# v0_2.net
KiCad netlist of a schematic drawn in EAGLE
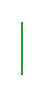
[diagram p0: schematic, sheet 1, part 1 of 2]
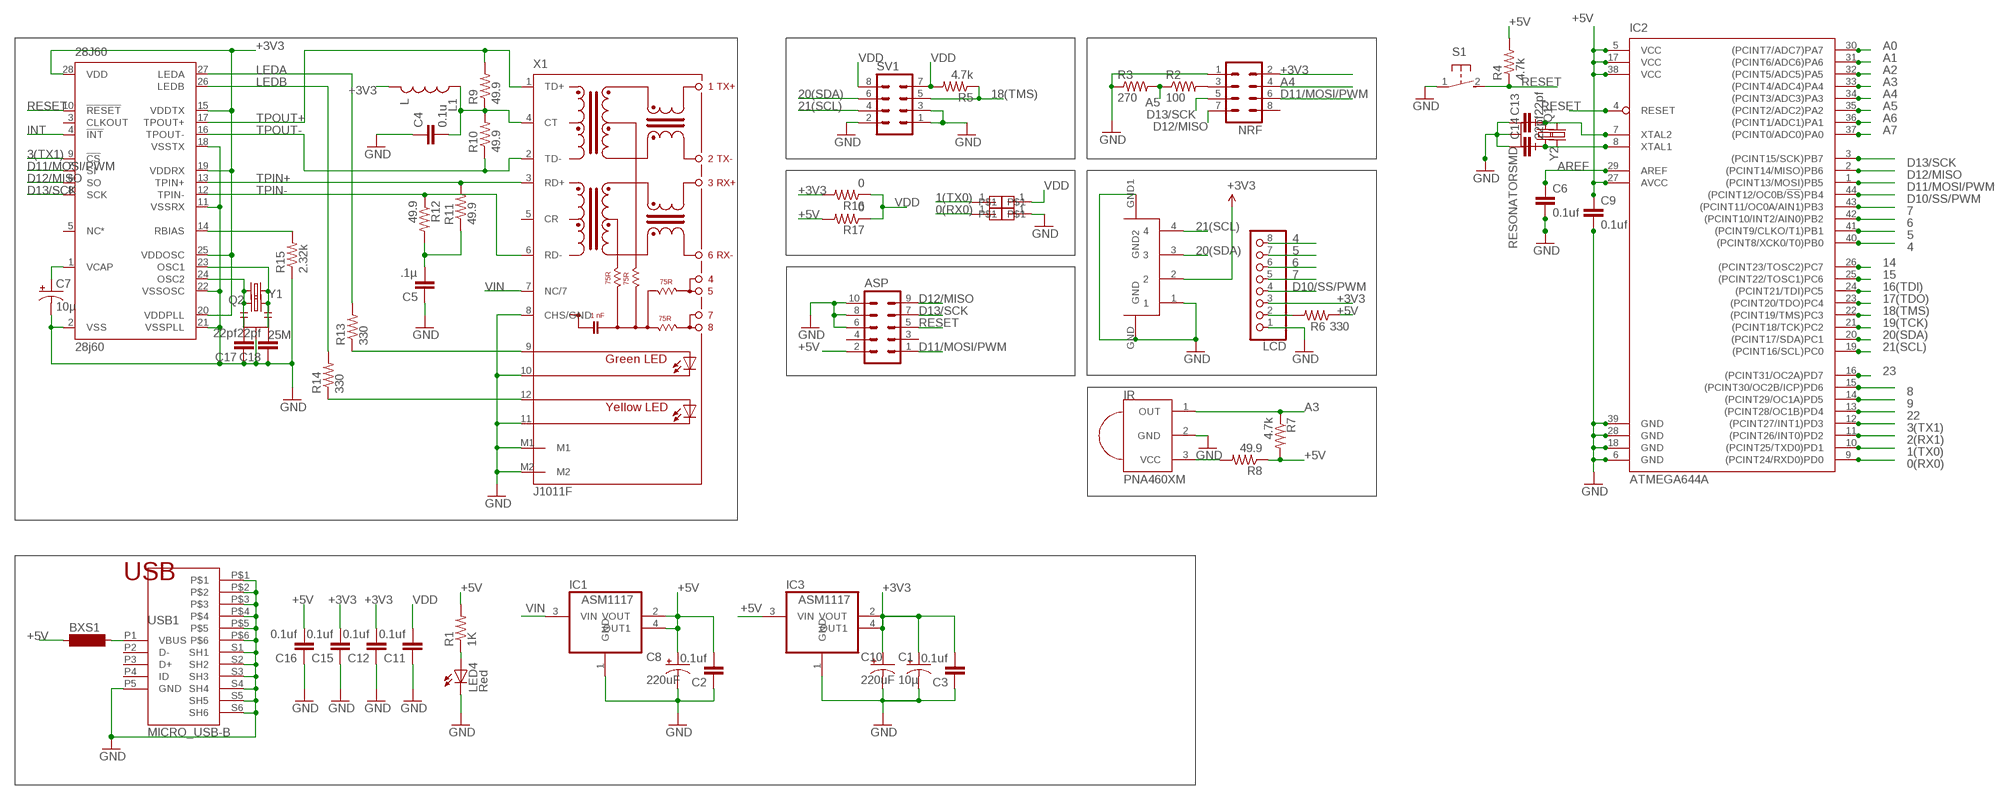
[diagram p1: schematic, sheet 1, part 2 of 2]

(export (version "E")
  (design (tool "Eeschema 10.0.6"))
  (components
    (comp (ref "28J60")
      (value "28j60")
      (footprint "eagle-import:SSOP28DB")
      (libsource (lib "eagle-import") (part "ENC28J60/SS"))
    )
    (comp (ref "ASP")
      (value "MA05-2")
      (footprint "eagle-import:MA05-2")
      (libsource (lib "eagle-import") (part "MA05-2"))
    )
    (comp (ref "BXS1")
      (value "SM-1206")
      (footprint "eagle-import:SM-1206")
      (fields (field (name "OC_FARNELL") "unknown") (field (name "OC_NEWARK") "unknown"))
      (libsource (lib "eagle-import") (part "SM-1206"))
    )
    (comp (ref "C1")
      (value "10µ")
      (footprint "eagle-import:EIA3528")
      (libsource (lib "eagle-import") (part "CAP_POL3528"))
    )
    (comp (ref "C2")
      (value "0.1uf")
      (footprint "eagle-import:0603-CAP")
      (libsource (lib "eagle-import") (part "MY_CAP0603-CAP"))
    )
    (comp (ref "C3")
      (value "0.1uf")
      (footprint "eagle-import:0603-CAP")
      (libsource (lib "eagle-import") (part "MY_CAP0603-CAP"))
    )
    (comp (ref "C4")
      (value "0.1u")
      (footprint "eagle-import:0603-CAP")
      (libsource (lib "eagle-import") (part "CAP0603-CAP"))
    )
    (comp (ref "C5")
      (value ".1µ")
      (footprint "eagle-import:0603-CAP")
      (libsource (lib "eagle-import") (part "CAP0603-CAP"))
    )
    (comp (ref "C6")
      (value "0.1uf")
      (footprint "eagle-import:0603-CAP")
      (libsource (lib "eagle-import") (part "CAP0603-CAP"))
    )
    (comp (ref "C7")
      (value "10µ")
      (footprint "eagle-import:EIA3528")
      (libsource (lib "eagle-import") (part "CAP_POL3528"))
    )
    (comp (ref "C8")
      (value "220uF")
      (footprint "eagle-import:153CLV-0605")
      (libsource (lib "eagle-import") (part "CPOL-US153CLV-0605"))
    )
    (comp (ref "C9")
      (value "0.1uf")
      (footprint "eagle-import:0603-CAP")
      (libsource (lib "eagle-import") (part "CAP0603-CAP"))
    )
    (comp (ref "C10")
      (value "220uF")
      (footprint "eagle-import:153CLV-0605")
      (libsource (lib "eagle-import") (part "CPOL-US153CLV-0605"))
    )
    (comp (ref "C11")
      (value "0.1uf")
      (footprint "eagle-import:0603-CAP")
      (libsource (lib "eagle-import") (part "MY_CAP0603-CAP"))
    )
    (comp (ref "C12")
      (value "0.1uf")
      (footprint "eagle-import:0603-CAP")
      (libsource (lib "eagle-import") (part "MY_CAP0603-CAP"))
    )
    (comp (ref "C13")
      (value "22pf")
      (footprint "eagle-import:0603-CAP")
      (libsource (lib "eagle-import") (part "CAP0603-CAP"))
    )
    (comp (ref "C14")
      (value "22pf")
      (footprint "eagle-import:0603-CAP")
      (libsource (lib "eagle-import") (part "CAP0603-CAP"))
    )
    (comp (ref "C15")
      (value "0.1uf")
      (footprint "eagle-import:0603-CAP")
      (libsource (lib "eagle-import") (part "MY_CAP0603-CAP"))
    )
    (comp (ref "C16")
      (value "0.1uf")
      (footprint "eagle-import:0603-CAP")
      (libsource (lib "eagle-import") (part "MY_CAP0603-CAP"))
    )
    (comp (ref "C17")
      (value "22pf")
      (footprint "eagle-import:0603-CAP")
      (libsource (lib "eagle-import") (part "CAP0603-CAP"))
    )
    (comp (ref "C18")
      (value "22pf")
      (footprint "eagle-import:0603-CAP")
      (libsource (lib "eagle-import") (part "CAP0603-CAP"))
    )
    (comp (ref "IC1")
      (value "ASM1117")
      (footprint "eagle-import:SOT223")
      (fields (field (name "MPN") "REG1117"))
      (libsource (lib "eagle-import") (part "ASM1117"))
    )
    (comp (ref "IC2")
      (value "ATMEGA644A")
      (footprint "eagle-import:TQFP44")
      (fields (field (name "MPN") "ATMEGA644PV-10AU"))
      (libsource (lib "eagle-import") (part "ATMEGA644A"))
    )
    (comp (ref "IC3")
      (value "ASM1117")
      (footprint "eagle-import:SOT223")
      (fields
        (field (name "MPN") "REG1117")
        (field (name "MPN_1") "REG1117")
        (field (name "OC_FARNELL") "1097566")
        (field (name "OC_NEWARK") "14P6981")
      )
      (libsource (lib "eagle-import") (part "ASM1117"))
    )
    (comp (ref "IR")
      (value "PNA460XM")
      (footprint "eagle-import:PNA460XM")
      (libsource (lib "eagle-import") (part "PNA460XM"))
    )
    (comp (ref "L1")
      (value "L")
      (footprint "eagle-import:0603")
      (libsource (lib "eagle-import") (part "INDUCTOR0603"))
    )
    (comp (ref "LCD")
      (value "PINHD-1X8")
      (footprint "eagle-import:1X08")
      (libsource (lib "eagle-import") (part "PINHD-1X8"))
    )
    (comp (ref "LED4")
      (value "Red")
      (footprint "eagle-import:0805-LED")
      (libsource (lib "eagle-import") (part "LED0805"))
    )
    (comp (ref "NRF")
      (value "MA04-2")
      (footprint "eagle-import:MA04-2")
      (libsource (lib "eagle-import") (part "MA04-2"))
    )
    (comp (ref "Q1")
      (value "CRYSTALHC49S")
      (footprint "eagle-import:HC49_S")
      (libsource (lib "eagle-import") (part "CRYSTALHC49S"))
    )
    (comp (ref "Q2")
      (value "CRYSTALHC49S")
      (footprint "eagle-import:HC49_S")
      (fields (field (name "OC_FARNELL") "1667008") (field (name "OC_NEWARK") "unknown"))
      (libsource (lib "eagle-import") (part "CRYSTALHC49S"))
    )
    (comp (ref "R1")
      (value "1K")
      (footprint "eagle-import:0603-RES")
      (libsource (lib "eagle-import") (part "MY_RESISTOR0603-RES"))
    )
    (comp (ref "R2")
      (value "100")
      (footprint "eagle-import:0603-RES")
      (libsource (lib "eagle-import") (part "MY_RESISTOR0603-RES"))
    )
    (comp (ref "R3")
      (value "270")
      (footprint "eagle-import:0603-RES")
      (libsource (lib "eagle-import") (part "MY_RESISTOR0603-RES"))
    )
    (comp (ref "R4")
      (value "4.7k")
      (footprint "eagle-import:0603-RES")
      (libsource (lib "eagle-import") (part "RESISTOR0603-RES"))
    )
    (comp (ref "R5")
      (value "4.7k")
      (footprint "eagle-import:0603-RES")
      (libsource (lib "eagle-import") (part "MY_RESISTOR0603-RES"))
    )
    (comp (ref "R6")
      (value "330")
      (footprint "eagle-import:0603-RES")
      (libsource (lib "eagle-import") (part "MY_RESISTOR0603-RES"))
    )
    (comp (ref "R7")
      (value "4.7k")
      (footprint "eagle-import:0603-RES")
      (libsource (lib "eagle-import") (part "MY_RESISTOR0603-RES"))
    )
    (comp (ref "R8")
      (value "49.9")
      (footprint "eagle-import:0603-RES")
      (libsource (lib "eagle-import") (part "MY_RESISTOR0603-RES"))
    )
    (comp (ref "R9")
      (value "49.9")
      (footprint "eagle-import:0603-RES")
      (libsource (lib "eagle-import") (part "RESISTOR0603-RES"))
    )
    (comp (ref "R10")
      (value "49.9")
      (footprint "eagle-import:0603-RES")
      (libsource (lib "eagle-import") (part "RESISTOR0603-RES"))
    )
    (comp (ref "R11")
      (value "49.9")
      (footprint "eagle-import:0603-RES")
      (libsource (lib "eagle-import") (part "RESISTOR0603-RES"))
    )
    (comp (ref "R12")
      (value "49.9")
      (footprint "eagle-import:0603-RES")
      (libsource (lib "eagle-import") (part "RESISTOR0603-RES"))
    )
    (comp (ref "R13")
      (value "330")
      (footprint "eagle-import:0603-RES")
      (libsource (lib "eagle-import") (part "RESISTOR0603-RES"))
    )
    (comp (ref "R14")
      (value "330")
      (footprint "eagle-import:0603-RES")
      (libsource (lib "eagle-import") (part "RESISTOR0603-RES"))
    )
    (comp (ref "R15")
      (value "2.32k")
      (footprint "eagle-import:0603-RES")
      (libsource (lib "eagle-import") (part "RESISTOR0603-RES"))
    )
    (comp (ref "R16")
      (value "0")
      (footprint "eagle-import:0603-RES")
      (libsource (lib "eagle-import") (part "MY_RESISTOR0603-RES"))
    )
    (comp (ref "R17")
      (value "0")
      (footprint "eagle-import:0603-RES")
      (libsource (lib "eagle-import") (part "MY_RESISTOR0603-RES"))
    )
    (comp (ref "S1")
      (value "31-XX")
      (footprint "eagle-import:B3F-31XX")
      (fields (field (name "MPN") "B3F-3100"))
      (libsource (lib "eagle-import") (part "31-XX"))
    )
    (comp (ref "SV1")
      (value "MA04-2")
      (footprint "eagle-import:MA04-2")
      (libsource (lib "eagle-import") (part "MA04-2"))
    )
    (comp (ref "U$2")
      (value "S4B-XH-SM4-TB")
      (footprint "eagle-import:XH-SM4-TB")
      (libsource (lib "eagle-import") (part "S4B-XH-SM4-TB"))
    )
    (comp (ref "U$4")
      (value "PIN1")
      (footprint "eagle-import:PIN1")
      (libsource (lib "eagle-import") (part "PIN1"))
    )
    (comp (ref "U$5")
      (value "PIN1")
      (footprint "eagle-import:PIN1")
      (libsource (lib "eagle-import") (part "PIN1"))
    )
    (comp (ref "U$6")
      (value "PIN1")
      (footprint "eagle-import:PIN1")
      (libsource (lib "eagle-import") (part "PIN1"))
    )
    (comp (ref "U$7")
      (value "PIN1")
      (footprint "eagle-import:PIN1")
      (libsource (lib "eagle-import") (part "PIN1"))
    )
    (comp (ref "USB1")
      (value "MICRO_USB-B")
      (footprint "eagle-import:USB_MICRO_B")
      (libsource (lib "eagle-import") (part "MICRO_USB-B"))
    )
    (comp (ref "X1")
      (value "J1011F")
      (footprint "eagle-import:HRJ")
      (libsource (lib "eagle-import") (part "RJ45-HR911105A"))
    )
    (comp (ref "Y1")
      (value "25M")
      (footprint "eagle-import:RESONATOR-SMD")
      (libsource (lib "eagle-import") (part "RESONATORSMD"))
    )
    (comp (ref "Y2")
      (value "RESONATORSMD")
      (footprint "eagle-import:RESONATOR-SMD")
      (libsource (lib "eagle-import") (part "MY_RESONATORSMD"))
    )
  )
  (nets
    (net (code "1") (name "+3V3") (class "Default")
      (node (ref "28J60") (pin "15") (pinfunction "VDDTX_15") (pintype "input"))
      (node (ref "28J60") (pin "19") (pinfunction "VDDRX_19") (pintype "input"))
      (node (ref "28J60") (pin "20") (pinfunction "VDDPLL_20") (pintype "input"))
      (node (ref "28J60") (pin "25") (pinfunction "VDDOSC_25") (pintype "input"))
      (node (ref "28J60") (pin "28") (pinfunction "VDD_28") (pintype "input"))
      (node (ref "C1") (pin "A") (pinfunction "+_A") (pintype "passive"))
      (node (ref "C10") (pin "+") (pinfunction "+_+") (pintype "passive"))
      (node (ref "C12") (pin "2") (pinfunction "2_2") (pintype "passive"))
      (node (ref "C15") (pin "2") (pinfunction "2_2") (pintype "passive"))
      (node (ref "C3") (pin "2") (pinfunction "2_2") (pintype "passive"))
      (node (ref "IC3") (pin "2") (pinfunction "VOUT_2") (pintype "output"))
      (node (ref "IC3") (pin "4") (pinfunction "OUT1_4") (pintype "bidirectional"))
      (node (ref "L1") (pin "2") (pinfunction "2_2") (pintype "passive"))
      (node (ref "LCD") (pin "3") (pinfunction "3_3") (pintype "passive"))
      (node (ref "NRF") (pin "2") (pinfunction "2_2") (pintype "passive"))
      (node (ref "R16") (pin "2") (pinfunction "2_2") (pintype "passive"))
      (node (ref "U$2") (pin "2") (pinfunction "2_2") (pintype "bidirectional"))
    )
    (net (code "2") (name "/+5V") (class "Default")
      (node (ref "ASP") (pin "2") (pinfunction "2_2") (pintype "passive"))
      (node (ref "BXS1") (pin "1") (pinfunction "1_1") (pintype "passive"))
      (node (ref "C16") (pin "2") (pinfunction "2_2") (pintype "passive"))
      (node (ref "C2") (pin "2") (pinfunction "2_2") (pintype "passive"))
      (node (ref "C8") (pin "+") (pinfunction "+_+") (pintype "passive"))
      (node (ref "C9") (pin "1") (pinfunction "1_1") (pintype "passive"))
      (node (ref "IC1") (pin "2") (pinfunction "VOUT_2") (pintype "output"))
      (node (ref "IC1") (pin "4") (pinfunction "OUT1_4") (pintype "bidirectional"))
      (node (ref "IC2") (pin "17") (pinfunction "VCC_17") (pintype "power_in"))
      (node (ref "IC2") (pin "27") (pinfunction "AVCC_27") (pintype "power_in"))
      (node (ref "IC2") (pin "38") (pinfunction "VCC_38") (pintype "power_in"))
      (node (ref "IC2") (pin "5") (pinfunction "VCC_5") (pintype "power_in"))
      (node (ref "IC3") (pin "3") (pinfunction "VIN_3") (pintype "input"))
      (node (ref "R1") (pin "2") (pinfunction "2_2") (pintype "passive"))
      (node (ref "R17") (pin "2") (pinfunction "2_2") (pintype "passive"))
      (node (ref "R4") (pin "2") (pinfunction "2_2") (pintype "passive"))
      (node (ref "R6") (pin "1") (pinfunction "1_1") (pintype "passive"))
      (node (ref "R7") (pin "2") (pinfunction "2_2") (pintype "passive"))
      (node (ref "R8") (pin "1") (pinfunction "1_1") (pintype "passive"))
    )
    (net (code "3") (name "/0(RX0)") (class "Default")
      (node (ref "IC2") (pin "9") (pinfunction "(PCINT24/RXD0)PD0_9") (pintype "bidirectional"))
      (node (ref "U$7") (pin "1") (pinfunction "P$1_1") (pintype "bidirectional"))
    )
    (net (code "4") (name "/1(TX0)") (class "Default")
      (node (ref "IC2") (pin "10") (pinfunction "(PCINT25/TXD0)PD1_10") (pintype "bidirectional"))
      (node (ref "U$6") (pin "1") (pinfunction "P$1_1") (pintype "bidirectional"))
    )
    (net (code "5") (name "/2(RX1)") (class "Default")
      (node (ref "IC2") (pin "11") (pinfunction "(PCINT26/INT0)PD2_11") (pintype "bidirectional"))
    )
    (net (code "6") (name "/3(TX1)") (class "Default")
      (node (ref "28J60") (pin "9") (pinfunction "~{CS}_9") (pintype "input"))
      (node (ref "IC2") (pin "12") (pinfunction "(PCINT27/INT1)PD3_12") (pintype "bidirectional"))
    )
    (net (code "7") (name "/4") (class "Default")
      (node (ref "IC2") (pin "40") (pinfunction "(PCINT8/XCK0/T0)PB0_40") (pintype "bidirectional"))
      (node (ref "LCD") (pin "8") (pinfunction "8_8") (pintype "passive"))
    )
    (net (code "8") (name "/5") (class "Default")
      (node (ref "IC2") (pin "41") (pinfunction "(PCINT9/CLKO/T1)PB1_41") (pintype "bidirectional"))
      (node (ref "LCD") (pin "7") (pinfunction "7_7") (pintype "passive"))
    )
    (net (code "9") (name "/6") (class "Default")
      (node (ref "IC2") (pin "42") (pinfunction "(PCINT10/INT2/AIN0)PB2_42") (pintype "bidirectional"))
      (node (ref "LCD") (pin "6") (pinfunction "6_6") (pintype "passive"))
    )
    (net (code "10") (name "/7") (class "Default")
      (node (ref "IC2") (pin "43") (pinfunction "(PCINT11/OC0A/AIN1)PB3_43") (pintype "bidirectional"))
      (node (ref "LCD") (pin "5") (pinfunction "5_5") (pintype "passive"))
    )
    (net (code "11") (name "/8") (class "Default")
      (node (ref "IC2") (pin "15") (pinfunction "(PCINT30/OC2B/ICP)PD6_15") (pintype "bidirectional"))
    )
    (net (code "12") (name "/9") (class "Default")
      (node (ref "IC2") (pin "14") (pinfunction "(PCINT29/OC1A)PD5_14") (pintype "bidirectional"))
    )
    (net (code "13") (name "/14") (class "Default")
      (node (ref "IC2") (pin "26") (pinfunction "(PCINT23/TOSC2)PC7_26") (pintype "output"))
    )
    (net (code "14") (name "/15") (class "Default")
      (node (ref "IC2") (pin "25") (pinfunction "(PCINT22/TOSC1)PC6_25") (pintype "output"))
    )
    (net (code "15") (name "/16(TDI)") (class "Default")
      (node (ref "IC2") (pin "24") (pinfunction "(PCINT21/TDI)PC5_24") (pintype "output"))
    )
    (net (code "16") (name "/17(TDO)") (class "Default")
      (node (ref "IC2") (pin "23") (pinfunction "(PCINT20/TDO)PC4_23") (pintype "output"))
    )
    (net (code "17") (name "/18(TMS)") (class "Default")
      (node (ref "IC2") (pin "22") (pinfunction "(PCINT19/TMS)PC3_22") (pintype "output"))
      (node (ref "R5") (pin "1") (pinfunction "1_1") (pintype "passive"))
      (node (ref "SV1") (pin "5") (pinfunction "5_5") (pintype "passive"))
    )
    (net (code "18") (name "/19(TCK)") (class "Default")
      (node (ref "IC2") (pin "21") (pinfunction "(PCINT18/TCK)PC2_21") (pintype "output"))
    )
    (net (code "19") (name "/20(SDA)") (class "Default")
      (node (ref "IC2") (pin "20") (pinfunction "(PCINT17/SDA)PC1_20") (pintype "output"))
      (node (ref "SV1") (pin "6") (pinfunction "6_6") (pintype "passive"))
      (node (ref "U$2") (pin "3") (pinfunction "3_3") (pintype "bidirectional"))
    )
    (net (code "20") (name "/21(SCL)") (class "Default")
      (node (ref "IC2") (pin "19") (pinfunction "(PCINT16/SCL)PC0_19") (pintype "output"))
      (node (ref "SV1") (pin "4") (pinfunction "4_4") (pintype "passive"))
      (node (ref "U$2") (pin "4") (pinfunction "4_4") (pintype "bidirectional"))
    )
    (net (code "21") (name "/22") (class "Default")
      (node (ref "IC2") (pin "13") (pinfunction "(PCINT28/OC1B)PD4_13") (pintype "bidirectional"))
    )
    (net (code "22") (name "/23") (class "Default")
      (node (ref "IC2") (pin "16") (pinfunction "(PCINT31/OC2A)PD7_16") (pintype "bidirectional"))
    )
    (net (code "23") (name "/A0") (class "Default")
      (node (ref "IC2") (pin "30") (pinfunction "(PCINT7/ADC7)PA7_30") (pintype "bidirectional"))
    )
    (net (code "24") (name "/A1") (class "Default")
      (node (ref "IC2") (pin "31") (pinfunction "(PCINT6/ADC6)PA6_31") (pintype "bidirectional"))
    )
    (net (code "25") (name "/A2") (class "Default")
      (node (ref "IC2") (pin "32") (pinfunction "(PCINT5/ADC5)PA5_32") (pintype "bidirectional"))
    )
    (net (code "26") (name "/A3") (class "Default")
      (node (ref "IC2") (pin "33") (pinfunction "(PCINT4/ADC4)PA4_33") (pintype "bidirectional"))
      (node (ref "IR") (pin "1") (pinfunction "OUT_1") (pintype "output"))
      (node (ref "R7") (pin "1") (pinfunction "1_1") (pintype "passive"))
    )
    (net (code "27") (name "/A4") (class "Default")
      (node (ref "IC2") (pin "34") (pinfunction "(PCINT3/ADC3)PA3_34") (pintype "bidirectional"))
      (node (ref "NRF") (pin "4") (pinfunction "4_4") (pintype "passive"))
    )
    (net (code "28") (name "/A5") (class "Default")
      (node (ref "IC2") (pin "35") (pinfunction "(PCINT2/ADC2)PA2_35") (pintype "bidirectional"))
      (node (ref "R2") (pin "1") (pinfunction "1_1") (pintype "passive"))
      (node (ref "R3") (pin "2") (pinfunction "2_2") (pintype "passive"))
    )
    (net (code "29") (name "/A6") (class "Default")
      (node (ref "IC2") (pin "36") (pinfunction "(PCINT1/ADC1)PA1_36") (pintype "bidirectional"))
    )
    (net (code "30") (name "/A7") (class "Default")
      (node (ref "IC2") (pin "37") (pinfunction "(PCINT0/ADC0)PA0_37") (pintype "bidirectional"))
    )
    (net (code "31") (name "/AREF") (class "Default")
      (node (ref "C6") (pin "1") (pinfunction "1_1") (pintype "passive"))
      (node (ref "IC2") (pin "29") (pinfunction "AREF_29") (pintype "passive"))
    )
    (net (code "32") (name "/D10{slash}SS{slash}PWM") (class "Default")
      (node (ref "IC2") (pin "44") (pinfunction "(PCINT12/OC0B/~{SS})PB4_44") (pintype "bidirectional"))
      (node (ref "LCD") (pin "4") (pinfunction "4_4") (pintype "passive"))
    )
    (net (code "33") (name "/D11{slash}MOSI{slash}PWM") (class "Default")
      (node (ref "28J60") (pin "7") (pinfunction "SI_7") (pintype "input"))
      (node (ref "ASP") (pin "1") (pinfunction "1_1") (pintype "passive"))
      (node (ref "IC2") (pin "1") (pinfunction "(PCINT13/MOSI)PB5_1") (pintype "bidirectional"))
      (node (ref "NRF") (pin "6") (pinfunction "6_6") (pintype "passive"))
    )
    (net (code "34") (name "/D12{slash}MISO") (class "Default")
      (node (ref "28J60") (pin "6") (pinfunction "SO_6") (pintype "output"))
      (node (ref "ASP") (pin "9") (pinfunction "9_9") (pintype "passive"))
      (node (ref "IC2") (pin "2") (pinfunction "(PCINT14/MISO)PB6_2") (pintype "bidirectional"))
      (node (ref "NRF") (pin "7") (pinfunction "7_7") (pintype "passive"))
    )
    (net (code "35") (name "/D13{slash}SCK") (class "Default")
      (node (ref "28J60") (pin "8") (pinfunction "SCK_8") (pintype "input"))
      (node (ref "ASP") (pin "7") (pinfunction "7_7") (pintype "passive"))
      (node (ref "IC2") (pin "3") (pinfunction "(PCINT15/SCK)PB7_3") (pintype "bidirectional"))
      (node (ref "NRF") (pin "5") (pinfunction "5_5") (pintype "passive"))
    )
    (net (code "36") (name "/INT") (class "Default")
      (node (ref "28J60") (pin "4") (pinfunction "~{INT}_4") (pintype "output"))
    )
    (net (code "37") (name "/LEDA") (class "Default")
      (node (ref "28J60") (pin "27") (pinfunction "LEDA_27") (pintype "output"))
      (node (ref "R13") (pin "2") (pinfunction "2_2") (pintype "passive"))
    )
    (net (code "38") (name "/LEDB") (class "Default")
      (node (ref "28J60") (pin "26") (pinfunction "LEDB_26") (pintype "output"))
      (node (ref "R14") (pin "2") (pinfunction "2_2") (pintype "passive"))
    )
    (net (code "39") (name "/RESET") (class "Default")
      (node (ref "28J60") (pin "10") (pinfunction "~{RESET}_10") (pintype "input"))
      (node (ref "ASP") (pin "5") (pinfunction "5_5") (pintype "passive"))
      (node (ref "IC2") (pin "4") (pinfunction "RESET_4") (pintype "input"))
      (node (ref "R4") (pin "1") (pinfunction "1_1") (pintype "passive"))
      (node (ref "S1") (pin "2") (pinfunction "S_2") (pintype "passive"))
    )
    (net (code "40") (name "/TPIN+") (class "Default")
      (node (ref "28J60") (pin "13") (pinfunction "TPIN+_13") (pintype "input"))
      (node (ref "R11") (pin "2") (pinfunction "2_2") (pintype "passive"))
      (node (ref "X1") (pin "3") (pinfunction "RD+_3") (pintype "input"))
    )
    (net (code "41") (name "/TPIN-") (class "Default")
      (node (ref "28J60") (pin "12") (pinfunction "TPIN-_12") (pintype "input"))
      (node (ref "R12") (pin "1") (pinfunction "1_1") (pintype "passive"))
      (node (ref "X1") (pin "6") (pinfunction "RD-_6") (pintype "input"))
    )
    (net (code "42") (name "/TPOUT+") (class "Default")
      (node (ref "28J60") (pin "17") (pinfunction "TPOUT+_17") (pintype "output"))
      (node (ref "R9") (pin "2") (pinfunction "2_2") (pintype "passive"))
      (node (ref "X1") (pin "1") (pinfunction "TD+_1") (pintype "input"))
    )
    (net (code "43") (name "/TPOUT-") (class "Default")
      (node (ref "28J60") (pin "16") (pinfunction "TPOUT-_16") (pintype "output"))
      (node (ref "R10") (pin "1") (pinfunction "1_1") (pintype "passive"))
      (node (ref "X1") (pin "2") (pinfunction "TD-_2") (pintype "input"))
    )
    (net (code "44") (name "/VDD") (class "Default")
      (node (ref "C11") (pin "2") (pinfunction "2_2") (pintype "passive"))
      (node (ref "R16") (pin "1") (pinfunction "1_1") (pintype "passive"))
      (node (ref "R17") (pin "1") (pinfunction "1_1") (pintype "passive"))
      (node (ref "R5") (pin "2") (pinfunction "2_2") (pintype "passive"))
      (node (ref "SV1") (pin "7") (pinfunction "7_7") (pintype "passive"))
      (node (ref "SV1") (pin "8") (pinfunction "8_8") (pintype "passive"))
      (node (ref "U$5") (pin "1") (pinfunction "P$1_1") (pintype "bidirectional"))
    )
    (net (code "45") (name "/VIN") (class "Default")
      (node (ref "IC1") (pin "3") (pinfunction "VIN_3") (pintype "input"))
      (node (ref "X1") (pin "7") (pinfunction "NC/7_7") (pintype "input"))
    )
    (net (code "46") (name "GND") (class "Default")
      (node (ref "28J60") (pin "11") (pinfunction "VSSRX_11") (pintype "input"))
      (node (ref "28J60") (pin "18") (pinfunction "VSSTX_18") (pintype "input"))
      (node (ref "28J60") (pin "2") (pinfunction "VSS_2") (pintype "input"))
      (node (ref "28J60") (pin "21") (pinfunction "VSSPLL_21") (pintype "input"))
      (node (ref "28J60") (pin "22") (pinfunction "VSSOSC_22") (pintype "input"))
      (node (ref "ASP") (pin "10") (pinfunction "10_10") (pintype "passive"))
      (node (ref "ASP") (pin "6") (pinfunction "6_6") (pintype "passive"))
      (node (ref "ASP") (pin "8") (pinfunction "8_8") (pintype "passive"))
      (node (ref "C1") (pin "C") (pinfunction "-_C") (pintype "passive"))
      (node (ref "C10") (pin "-") (pinfunction "-_-") (pintype "passive"))
      (node (ref "C11") (pin "1") (pinfunction "1_1") (pintype "passive"))
      (node (ref "C12") (pin "1") (pinfunction "1_1") (pintype "passive"))
      (node (ref "C13") (pin "1") (pinfunction "1_1") (pintype "passive"))
      (node (ref "C14") (pin "1") (pinfunction "1_1") (pintype "passive"))
      (node (ref "C15") (pin "1") (pinfunction "1_1") (pintype "passive"))
      (node (ref "C16") (pin "1") (pinfunction "1_1") (pintype "passive"))
      (node (ref "C17") (pin "1") (pinfunction "1_1") (pintype "passive"))
      (node (ref "C18") (pin "1") (pinfunction "1_1") (pintype "passive"))
      (node (ref "C2") (pin "1") (pinfunction "1_1") (pintype "passive"))
      (node (ref "C3") (pin "1") (pinfunction "1_1") (pintype "passive"))
      (node (ref "C4") (pin "1") (pinfunction "1_1") (pintype "passive"))
      (node (ref "C5") (pin "1") (pinfunction "1_1") (pintype "passive"))
      (node (ref "C6") (pin "2") (pinfunction "2_2") (pintype "passive"))
      (node (ref "C7") (pin "C") (pinfunction "-_C") (pintype "passive"))
      (node (ref "C8") (pin "-") (pinfunction "-_-") (pintype "passive"))
      (node (ref "C9") (pin "2") (pinfunction "2_2") (pintype "passive"))
      (node (ref "IC1") (pin "1") (pinfunction "GND_1") (pintype "power_in"))
      (node (ref "IC2") (pin "18") (pinfunction "GND_18") (pintype "power_in"))
      (node (ref "IC2") (pin "28") (pinfunction "GND_28") (pintype "power_in"))
      (node (ref "IC2") (pin "39") (pinfunction "GND_39") (pintype "power_in"))
      (node (ref "IC2") (pin "6") (pinfunction "GND_6") (pintype "power_in"))
      (node (ref "IC3") (pin "1") (pinfunction "GND_1") (pintype "power_in"))
      (node (ref "IR") (pin "2") (pinfunction "GND_2") (pintype "power_in"))
      (node (ref "LCD") (pin "1") (pinfunction "1_1") (pintype "passive"))
      (node (ref "LED4") (pin "C") (pinfunction "C_C") (pintype "passive"))
      (node (ref "NRF") (pin "1") (pinfunction "1_1") (pintype "passive"))
      (node (ref "R15") (pin "1") (pinfunction "1_1") (pintype "passive"))
      (node (ref "R3") (pin "1") (pinfunction "1_1") (pintype "passive"))
      (node (ref "S1") (pin "1") (pinfunction "P_1") (pintype "passive"))
      (node (ref "SV1") (pin "1") (pinfunction "1_1") (pintype "passive"))
      (node (ref "SV1") (pin "2") (pinfunction "2_2") (pintype "passive"))
      (node (ref "SV1") (pin "3") (pinfunction "3_3") (pintype "passive"))
      (node (ref "U$2") (pin "1") (pinfunction "1_1") (pintype "bidirectional"))
      (node (ref "U$2") (pin "GND") (pinfunction "GND_GND") (pintype "bidirectional"))
      (node (ref "U$2") (pin "GND1") (pinfunction "GND2_GND1") (pintype "bidirectional"))
      (node (ref "U$4") (pin "1") (pinfunction "P$1_1") (pintype "bidirectional"))
      (node (ref "USB1") (pin "P$1") (pinfunction "P$1_P$1") (pintype "bidirectional"))
      (node (ref "USB1") (pin "P$2") (pinfunction "P$2_P$2") (pintype "bidirectional"))
      (node (ref "USB1") (pin "P$3") (pinfunction "P$3_P$3") (pintype "bidirectional"))
      (node (ref "USB1") (pin "P$4") (pinfunction "P$4_P$4") (pintype "bidirectional"))
      (node (ref "USB1") (pin "P$5") (pinfunction "P$5_P$5") (pintype "bidirectional"))
      (node (ref "USB1") (pin "P$6") (pinfunction "P$6_P$6") (pintype "bidirectional"))
      (node (ref "USB1") (pin "P5") (pinfunction "GND_P5") (pintype "passive"))
      (node (ref "USB1") (pin "S1") (pinfunction "SH1_S1") (pintype "passive"))
      (node (ref "USB1") (pin "S2") (pinfunction "SH2_S2") (pintype "passive"))
      (node (ref "USB1") (pin "S3") (pinfunction "SH3_S3") (pintype "passive"))
      (node (ref "USB1") (pin "S4") (pinfunction "SH4_S4") (pintype "passive"))
      (node (ref "USB1") (pin "S5") (pinfunction "SH5_S5") (pintype "passive"))
      (node (ref "USB1") (pin "S6") (pinfunction "SH6_S6") (pintype "passive"))
      (node (ref "X1") (pin "10") (pinfunction "C-R_10") (pintype "passive"))
      (node (ref "X1") (pin "11") (pinfunction "C-L_11") (pintype "passive"))
      (node (ref "X1") (pin "8") (pinfunction "CHS/GND_8") (pintype "input"))
      (node (ref "X1") (pin "M1") (pinfunction "M1_M1") (pintype "bidirectional"))
      (node (ref "X1") (pin "M2") (pinfunction "M2_M2") (pintype "bidirectional"))
      (node (ref "Y1") (pin "2") (pinfunction "2_2") (pintype "passive"))
      (node (ref "Y2") (pin "2") (pinfunction "2_2") (pintype "passive"))
    )
    (net (code "47") (name "Net-(28J60-OSC1)") (class "Default")
      (node (ref "28J60") (pin "23") (pinfunction "OSC1_23") (pintype "input"))
      (node (ref "C18") (pin "2") (pinfunction "2_2") (pintype "passive"))
      (node (ref "Q2") (pin "1") (pinfunction "1_1") (pintype "passive"))
      (node (ref "Y1") (pin "3") (pinfunction "3_3") (pintype "passive"))
    )
    (net (code "48") (name "Net-(28J60-OSC2)") (class "Default")
      (node (ref "28J60") (pin "24") (pinfunction "OSC2_24") (pintype "output"))
      (node (ref "C17") (pin "2") (pinfunction "2_2") (pintype "passive"))
      (node (ref "Q2") (pin "2") (pinfunction "2_2") (pintype "passive"))
      (node (ref "Y1") (pin "1") (pinfunction "1_1") (pintype "passive"))
    )
    (net (code "49") (name "Net-(28J60-RBIAS)") (class "Default")
      (node (ref "28J60") (pin "14") (pinfunction "RBIAS_14") (pintype "input"))
      (node (ref "R15") (pin "2") (pinfunction "2_2") (pintype "passive"))
    )
    (net (code "50") (name "Net-(28J60-VCAP)") (class "Default")
      (node (ref "28J60") (pin "1") (pinfunction "VCAP_1") (pintype "input"))
      (node (ref "C7") (pin "A") (pinfunction "+_A") (pintype "passive"))
    )
    (net (code "51") (name "Net-(C5-Pad2)") (class "Default")
      (node (ref "C5") (pin "2") (pinfunction "2_2") (pintype "passive"))
      (node (ref "R11") (pin "1") (pinfunction "1_1") (pintype "passive"))
      (node (ref "R12") (pin "2") (pinfunction "2_2") (pintype "passive"))
    )
    (net (code "52") (name "Net-(IC2-XTAL1)") (class "Default")
      (node (ref "C14") (pin "2") (pinfunction "2_2") (pintype "passive"))
      (node (ref "IC2") (pin "8") (pinfunction "XTAL1_8") (pintype "bidirectional"))
      (node (ref "Q1") (pin "1") (pinfunction "1_1") (pintype "passive"))
      (node (ref "Y2") (pin "3") (pinfunction "3_3") (pintype "passive"))
    )
    (net (code "53") (name "Net-(IC2-XTAL2)") (class "Default")
      (node (ref "C13") (pin "2") (pinfunction "2_2") (pintype "passive"))
      (node (ref "IC2") (pin "7") (pinfunction "XTAL2_7") (pintype "bidirectional"))
      (node (ref "Q1") (pin "2") (pinfunction "2_2") (pintype "passive"))
      (node (ref "Y2") (pin "1") (pinfunction "1_1") (pintype "passive"))
    )
    (net (code "54") (name "Net-(IR-VCC)") (class "Default")
      (node (ref "IR") (pin "3") (pinfunction "VCC_3") (pintype "power_in"))
      (node (ref "R8") (pin "2") (pinfunction "2_2") (pintype "passive"))
    )
    (net (code "55") (name "Net-(LCD-Pad2)") (class "Default")
      (node (ref "LCD") (pin "2") (pinfunction "2_2") (pintype "passive"))
      (node (ref "R6") (pin "2") (pinfunction "2_2") (pintype "passive"))
    )
    (net (code "56") (name "Net-(LED4-PadA)") (class "Default")
      (node (ref "LED4") (pin "A") (pinfunction "A_A") (pintype "passive"))
      (node (ref "R1") (pin "1") (pinfunction "1_1") (pintype "passive"))
    )
    (net (code "57") (name "Net-(NRF-Pad3)") (class "Default")
      (node (ref "NRF") (pin "3") (pinfunction "3_3") (pintype "passive"))
      (node (ref "R2") (pin "2") (pinfunction "2_2") (pintype "passive"))
    )
    (net (code "58") (name "Net-(USB1-VBUS)") (class "Default")
      (node (ref "BXS1") (pin "2") (pinfunction "2_2") (pintype "passive"))
      (node (ref "USB1") (pin "P1") (pinfunction "VBUS_P1") (pintype "power_in"))
    )
    (net (code "59") (name "Net-(X1-A-R)") (class "Default")
      (node (ref "R13") (pin "1") (pinfunction "1_1") (pintype "passive"))
      (node (ref "X1") (pin "9") (pinfunction "A-R_9") (pintype "passive"))
    )
    (net (code "60") (name "Net-(X1-AL)") (class "Default")
      (node (ref "R14") (pin "1") (pinfunction "1_1") (pintype "passive"))
      (node (ref "X1") (pin "12") (pinfunction "AL_12") (pintype "passive"))
    )
    (net (code "61") (name "Net-(X1-CT)") (class "Default")
      (node (ref "C4") (pin "2") (pinfunction "2_2") (pintype "passive"))
      (node (ref "L1") (pin "1") (pinfunction "1_1") (pintype "passive"))
      (node (ref "R10") (pin "2") (pinfunction "2_2") (pintype "passive"))
      (node (ref "R9") (pin "1") (pinfunction "1_1") (pintype "passive"))
      (node (ref "X1") (pin "4") (pinfunction "CT_4") (pintype "input"))
    )
    (net (code "62") (name "unconnected-(28J60-CLKOUT-Pad3)") (class "Default")
      (node (ref "28J60") (pin "3") (pinfunction "CLKOUT_3") (pintype "output"))
    )
    (net (code "63") (name "unconnected-(28J60-NC*-Pad5)") (class "Default")
      (node (ref "28J60") (pin "5") (pinfunction "NC*_5") (pintype "output"))
    )
    (net (code "64") (name "unconnected-(ASP-Pad3)") (class "Default")
      (node (ref "ASP") (pin "3") (pinfunction "3_3") (pintype "passive"))
    )
    (net (code "65") (name "unconnected-(ASP-Pad4)") (class "Default")
      (node (ref "ASP") (pin "4") (pinfunction "4_4") (pintype "passive"))
    )
    (net (code "66") (name "unconnected-(NRF-Pad8)") (class "Default")
      (node (ref "NRF") (pin "8") (pinfunction "8_8") (pintype "passive"))
    )
    (net (code "67") (name "unconnected-(USB1-D+-PadP3)") (class "Default")
      (node (ref "USB1") (pin "P3") (pinfunction "D+_P3") (pintype "bidirectional"))
    )
    (net (code "68") (name "unconnected-(USB1-D--PadP2)") (class "Default")
      (node (ref "USB1") (pin "P2") (pinfunction "D-_P2") (pintype "bidirectional"))
    )
    (net (code "69") (name "unconnected-(USB1-ID-PadP4)") (class "Default")
      (node (ref "USB1") (pin "P4") (pinfunction "ID_P4") (pintype "bidirectional"))
    )
    (net (code "70") (name "unconnected-(X1-CR-Pad5)") (class "Default")
      (node (ref "X1") (pin "5") (pinfunction "CR_5") (pintype "input"))
    )
  )
)
